# DogBLDC.net
KiCad netlist of a schematic drawn in Altium Designer
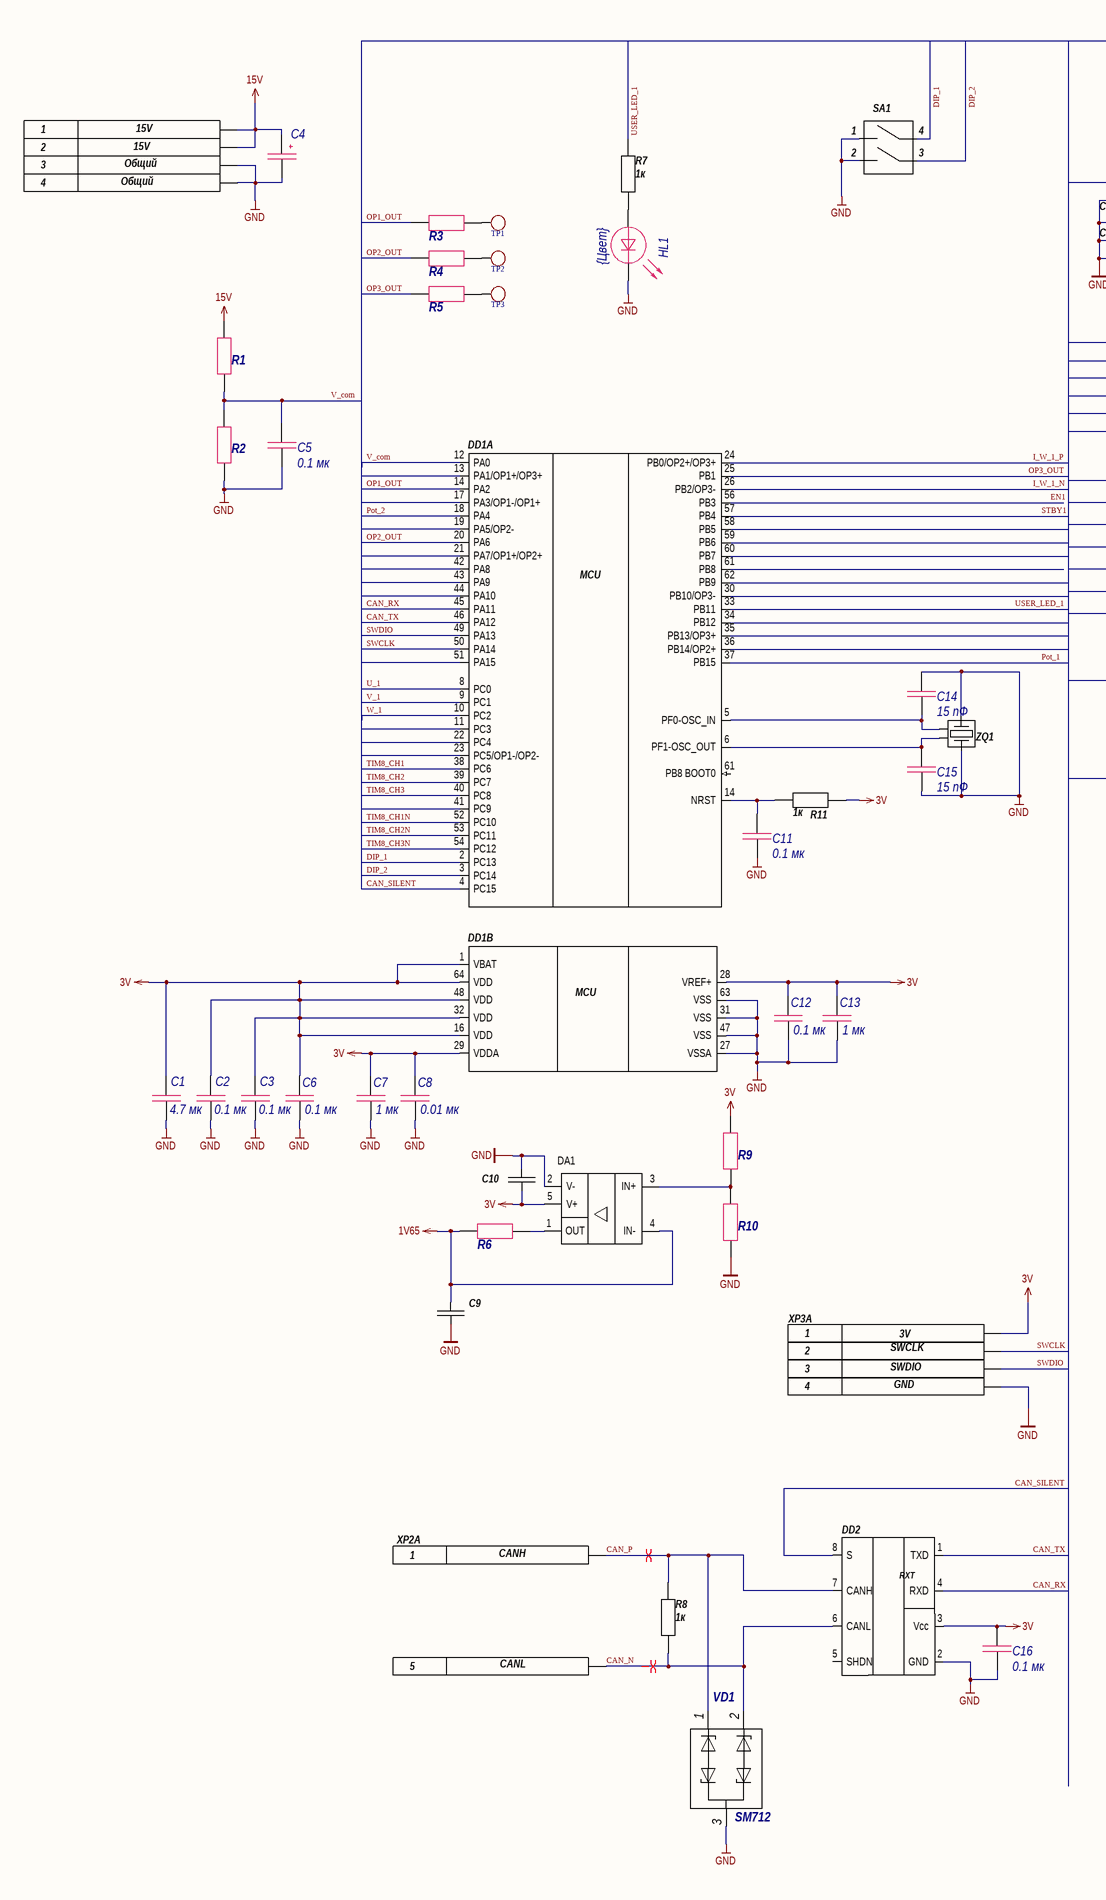
[diagram p0: DogBLDC.SchDoc, left]
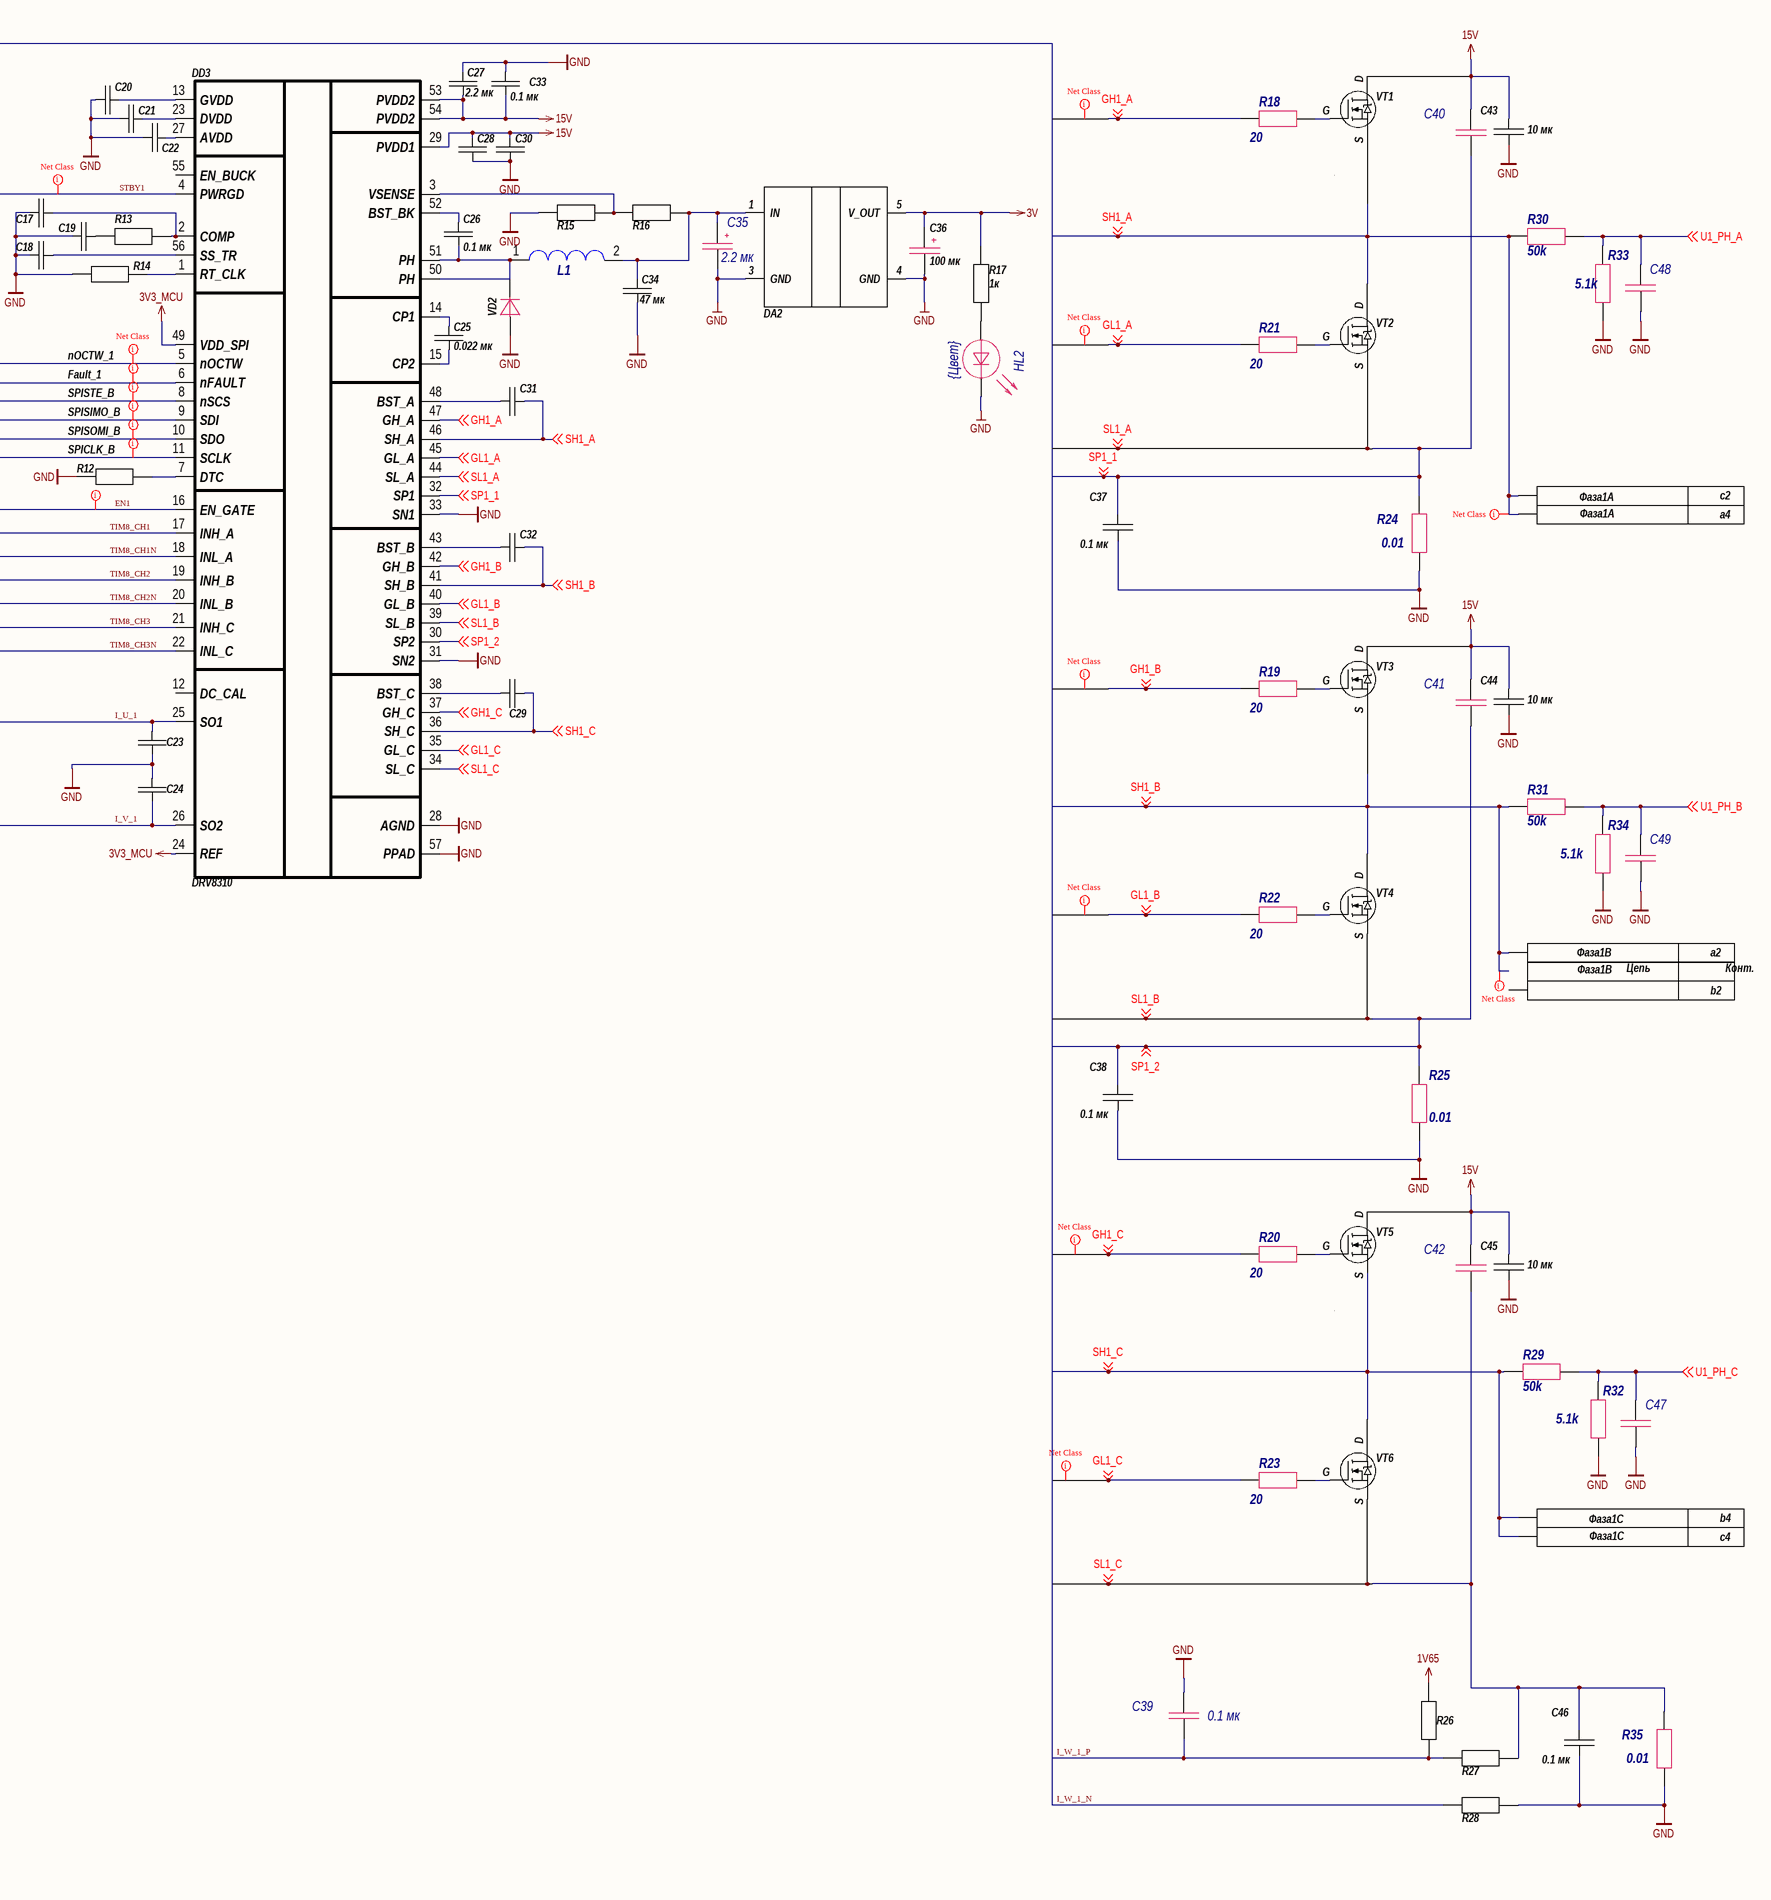
[diagram p1: DogBLDC.SchDoc, right]

(export (version "E")
  (design (tool "Eeschema 10.0.6"))
  (components
    (comp (ref "C1")
      (value "4.7 мк")
      (footprint "0603cap")
      (description "Capacitor")
      (libsource (lib "DogBLDC") (part "Capacitor"))
    )
    (comp (ref "C2")
      (value "0.1 мк")
      (footprint "0603cap")
      (description "Capacitor")
      (libsource (lib "DogBLDC") (part "Capacitor"))
    )
    (comp (ref "C3")
      (value "0.1 мк")
      (footprint "0603cap")
      (description "Capacitor")
      (libsource (lib "DogBLDC") (part "Capacitor"))
    )
    (comp (ref "C4")
      (value "1uF")
      (footprint "TC_B (3528)")
      (libsource (lib "DogBLDC") (part "Capacitor_pol"))
    )
    (comp (ref "C5")
      (value "0.1 мк")
      (footprint "0603c")
      (description "Capacitor")
      (libsource (lib "DogBLDC") (part "Capacitor"))
    )
    (comp (ref "C6")
      (value "0.1 мк")
      (footprint "0603cap")
      (description "Capacitor")
      (libsource (lib "DogBLDC") (part "Capacitor"))
    )
    (comp (ref "C7")
      (value "1 мк")
      (footprint "0603cap")
      (description "Capacitor")
      (libsource (lib "DogBLDC") (part "Capacitor"))
    )
    (comp (ref "C8")
      (value "0.01 мк")
      (footprint "0603cap")
      (description "Capacitor")
      (libsource (lib "DogBLDC") (part "Capacitor"))
    )
    (comp (ref "C9")
      (value "C_1")
      (footprint "RES 0402")
      (fields (field (name "TOLERANCE") "10 %"))
      (libsource (lib "DogBLDC") (part "C_1"))
    )
    (comp (ref "C10")
      (value "C_1")
      (footprint "RES 0402")
      (fields (field (name "TOLERANCE") "10 %"))
      (libsource (lib "DogBLDC") (part "C_1"))
    )
    (comp (ref "C11")
      (value "0.1 мк")
      (footprint "0603cap")
      (description "Capacitor")
      (libsource (lib "DogBLDC") (part "Capacitor"))
    )
    (comp (ref "C12")
      (value "0.1 мк")
      (footprint "0603cap")
      (description "Capacitor")
      (libsource (lib "DogBLDC") (part "Capacitor"))
    )
    (comp (ref "C13")
      (value "1 мк")
      (footprint "0603cap")
      (description "Capacitor")
      (libsource (lib "DogBLDC") (part "Capacitor"))
    )
    (comp (ref "C14")
      (value "15 пФ")
      (footprint "0603cap")
      (description "Capacitor")
      (libsource (lib "DogBLDC") (part "Capacitor"))
    )
    (comp (ref "C15")
      (value "15 пФ")
      (footprint "0603cap")
      (description "Capacitor")
      (libsource (lib "DogBLDC") (part "Capacitor"))
    )
    (comp (ref "C16")
      (value "0.1 мк")
      (footprint "0603cap")
      (description "Capacitor")
      (libsource (lib "DogBLDC") (part "Capacitor"))
    )
    (comp (ref "C17")
      (value "C_1")
      (footprint "RES 0402")
      (fields (field (name "TOLERANCE") "5 %"))
      (libsource (lib "DogBLDC") (part "C_1"))
    )
    (comp (ref "C18")
      (value "C_1")
      (footprint "RES 0402")
      (fields (field (name "TOLERANCE") "5 %"))
      (libsource (lib "DogBLDC") (part "C_1"))
    )
    (comp (ref "C19")
      (value "C_1")
      (footprint "RES 0402")
      (fields (field (name "TOLERANCE") "10 %"))
      (libsource (lib "DogBLDC") (part "C_1"))
    )
    (comp (ref "C20")
      (value "C_1")
      (footprint "0603c")
      (fields (field (name "TOLERANCE") "10 %"))
      (libsource (lib "DogBLDC") (part "C_1"))
    )
    (comp (ref "C21")
      (value "C_1")
      (footprint "0603c")
      (fields (field (name "TOLERANCE") "10 %"))
      (libsource (lib "DogBLDC") (part "C_1"))
    )
    (comp (ref "C22")
      (value "C_1")
      (footprint "0603c")
      (fields (field (name "TOLERANCE") "10 %"))
      (libsource (lib "DogBLDC") (part "C_1"))
    )
    (comp (ref "C23")
      (value "C_1")
      (footprint "RES 0402")
      (fields (field (name "TOLERANCE") "10 %"))
      (libsource (lib "DogBLDC") (part "C_1"))
    )
    (comp (ref "C24")
      (value "C_1")
      (footprint "RES 0402")
      (fields (field (name "TOLERANCE") "10 %"))
      (libsource (lib "DogBLDC") (part "C_1"))
    )
    (comp (ref "C25")
      (value "0.022 мк")
      (footprint "0805")
      (fields (field (name "TOLERANCE") "10 %") (field (name "Comment") "C_1"))
      (libsource (lib "DogBLDC") (part "C_1"))
    )
    (comp (ref "C26")
      (value "0.1 мк")
      (footprint "0603cap")
      (fields (field (name "TOLERANCE") "10 %") (field (name "Comment") "C_1"))
      (libsource (lib "DogBLDC") (part "C_1"))
    )
    (comp (ref "C27")
      (value "2.2 мк")
      (footprint "1206 - duplicate")
      (fields (field (name "TOLERANCE") "10 %") (field (name "Comment") "C_1"))
      (libsource (lib "DogBLDC") (part "C_1"))
    )
    (comp (ref "C28")
      (value "C_1")
      (footprint "0603cap")
      (fields (field (name "TOLERANCE") "10 %"))
      (libsource (lib "DogBLDC") (part "C_1"))
    )
    (comp (ref "C29")
      (value "C_1")
      (footprint "0603cap")
      (fields (field (name "TOLERANCE") "10 %"))
      (libsource (lib "DogBLDC") (part "C_1"))
    )
    (comp (ref "C30")
      (value "C_1")
      (footprint "0603cap")
      (fields (field (name "TOLERANCE") "10 %"))
      (libsource (lib "DogBLDC") (part "C_1"))
    )
    (comp (ref "C31")
      (value "C_1")
      (footprint "0603cap")
      (fields (field (name "TOLERANCE") "10 %"))
      (libsource (lib "DogBLDC") (part "C_1"))
    )
    (comp (ref "C32")
      (value "C_1")
      (footprint "0603cap")
      (fields (field (name "TOLERANCE") "10 %"))
      (libsource (lib "DogBLDC") (part "C_1"))
    )
    (comp (ref "C33")
      (value "0.1 мк")
      (footprint "0603cap")
      (fields (field (name "TOLERANCE") "10 %") (field (name "Comment") "C_1"))
      (libsource (lib "DogBLDC") (part "C_1"))
    )
    (comp (ref "C34")
      (value "47 мк")
      (footprint "1206 - duplicate")
      (fields (field (name "TOLERANCE") "10 %") (field (name "Comment") "C_1"))
      (libsource (lib "DogBLDC") (part "C_1"))
    )
    (comp (ref "C35")
      (value "2.2 мк")
      (footprint "TC_A (3216)")
      (fields (field (name "Comment") "1uF"))
      (libsource (lib "DogBLDC") (part "Capacitor_pol"))
    )
    (comp (ref "C36")
      (value "100 мк")
      (footprint "TC_D (7343)")
      (fields (field (name "TOLERANCE") "10 %") (field (name "Comment") "1uF"))
      (libsource (lib "DogBLDC") (part "Capacitor_pol"))
    )
    (comp (ref "C37")
      (value "0.1 мк")
      (footprint "0603C")
      (fields (field (name "TOLERANCE") "10 %"))
      (libsource (lib "DogBLDC") (part "C"))
    )
    (comp (ref "C38")
      (value "0.1 мк")
      (footprint "0603C")
      (fields (field (name "TOLERANCE") "10 %"))
      (libsource (lib "DogBLDC") (part "C"))
    )
    (comp (ref "C39")
      (value "0.1 мк")
      (footprint "0603C")
      (description "Capacitor")
      (fields (field (name "TOLERANCE") "10 %"))
      (libsource (lib "DogBLDC") (part "Capacitor"))
    )
    (comp (ref "C40")
      (value "Capacitor")
      (footprint "CAP_2220")
      (libsource (lib "DogBLDC") (part "Capacitor"))
    )
    (comp (ref "C41")
      (value "Capacitor")
      (footprint "CAP_2220")
      (libsource (lib "DogBLDC") (part "Capacitor"))
    )
    (comp (ref "C42")
      (value "Capacitor")
      (footprint "CAP_2220")
      (libsource (lib "DogBLDC") (part "Capacitor"))
    )
    (comp (ref "C43")
      (value "10 мк")
      (footprint "1812С")
      (fields (field (name "TOLERANCE") "10 %"))
      (libsource (lib "DogBLDC") (part "C"))
    )
    (comp (ref "C44")
      (value "10 мк")
      (footprint "1812С")
      (fields (field (name "TOLERANCE") "10 %"))
      (libsource (lib "DogBLDC") (part "C"))
    )
    (comp (ref "C45")
      (value "10 мк")
      (footprint "1812С")
      (fields (field (name "TOLERANCE") "10 %"))
      (libsource (lib "DogBLDC") (part "C"))
    )
    (comp (ref "C46")
      (value "0.1 мк")
      (footprint "0603C")
      (fields (field (name "TOLERANCE") "10 %"))
      (libsource (lib "DogBLDC") (part "C"))
    )
    (comp (ref "C47")
      (value "Capacitor")
      (footprint "RES 0402")
      (fields (field (name "TOLERANCE") "10 %"))
      (libsource (lib "DogBLDC") (part "Capacitor"))
    )
    (comp (ref "C48")
      (value "Capacitor")
      (footprint "RES 0402")
      (fields (field (name "TOLERANCE") "10 %"))
      (libsource (lib "DogBLDC") (part "Capacitor"))
    )
    (comp (ref "C49")
      (value "Capacitor")
      (footprint "RES 0402")
      (fields (field (name "TOLERANCE") "10 %"))
      (libsource (lib "DogBLDC") (part "Capacitor"))
    )
    (comp (ref "DA1") (value "TLV2781") (footprint "SOT23-5") (libsource (lib "DogBLDC") (part "TLV2781")))
    (comp (ref "DA2")
      (value "TPS7B9xx")
      (footprint "SOT23_6_Pin")
      (libsource (lib "DogBLDC") (part "TPS7B9xx"))
    )
    (comp (ref "DD1")
      (value "STM32G431x6")
      (footprint "STM-LQFP64_L")
      (fields (field (name "MANUFACTURER") "STMicroelectronics") (field (name "PARTNUMBER") "STM32F407VET6"))
      (libsource (lib "DogBLDC") (part "STM32G431x6"))
    )
    (comp (ref "DD2")
      (value "TCAN337DCN")
      (footprint "SOT23-8")
      (libsource (lib "DogBLDC") (part "TCAN337DCN"))
    )
    (comp (ref "DD3")
      (value "DRV8310")
      (footprint "TSSOP50P810X120_HS-57N")
      (libsource (lib "DogBLDC") (part "DRV8301"))
    )
    (comp (ref "HL1")
      (value "~")
      (footprint "0603D")
      (fields (field (name "COLOR") "{Цвет}"))
      (libsource (lib "DogBLDC") (part "LED"))
    )
    (comp (ref "HL2")
      (value "~")
      (footprint "0603D")
      (fields (field (name "COLOR") "{Цвет}"))
      (libsource (lib "DogBLDC") (part "LED"))
    )
    (comp (ref "L1")
      (value "DR74-330-R")
      (footprint "Inductor 6.3x6.3")
      (libsource (lib "DogBLDC") (part "Inductance"))
    )
    (comp (ref "R1")
      (value "Resistor")
      (footprint "RES 0402")
      (fields (field (name "TOLERANCE") "5 %"))
      (libsource (lib "") (part "Resistor_3"))
    )
    (comp (ref "R2")
      (value "Resistor")
      (footprint "RES 0402")
      (fields (field (name "TOLERANCE") "5 %"))
      (libsource (lib "") (part "Resistor_3"))
    )
    (comp (ref "R3")
      (value "Resistor")
      (footprint "RES 0402")
      (fields (field (name "TOLERANCE") "5 %"))
      (libsource (lib "") (part "Resistor_1"))
    )
    (comp (ref "R4")
      (value "Resistor")
      (footprint "RES 0402")
      (fields (field (name "TOLERANCE") "5 %"))
      (libsource (lib "") (part "Resistor_1"))
    )
    (comp (ref "R5")
      (value "Resistor")
      (footprint "RES 0402")
      (fields (field (name "TOLERANCE") "5 %"))
      (libsource (lib "") (part "Resistor_1"))
    )
    (comp (ref "R6")
      (value "Resistor")
      (footprint "RES 0402")
      (fields (field (name "TOLERANCE") "5 %"))
      (libsource (lib "") (part "Resistor_1"))
    )
    (comp (ref "R7")
      (value "1к")
      (footprint "0603res")
      (description "Resistor")
      (libsource (lib "") (part "Resistor_2"))
    )
    (comp (ref "R8")
      (value "1к")
      (footprint "0603res")
      (description "Resistor")
      (libsource (lib "") (part "Resistor_2"))
    )
    (comp (ref "R9")
      (value "Resistor")
      (footprint "RES 0402")
      (fields (field (name "TOLERANCE") "0.1%"))
      (libsource (lib "") (part "Resistor_2"))
    )
    (comp (ref "R10")
      (value "Resistor")
      (footprint "RES 0402")
      (fields (field (name "TOLERANCE") "0.1%"))
      (libsource (lib "") (part "Resistor_2"))
    )
    (comp (ref "R11")
      (value "1к")
      (footprint "0603res")
      (description "Resistor")
      (libsource (lib "") (part "Resistor_1"))
    )
    (comp (ref "R12")
      (value "Resistor")
      (footprint "RES 0402")
      (fields (field (name "TOLERANCE") "10 %"))
      (libsource (lib "DogBLDC") (part "Resistor"))
    )
    (comp (ref "R13")
      (value "Resistor")
      (footprint "RES 0402")
      (fields (field (name "TOLERANCE") "0.1 %"))
      (libsource (lib "DogBLDC") (part "Resistor"))
    )
    (comp (ref "R14")
      (value "Resistor")
      (footprint "RES 0402")
      (fields (field (name "TOLERANCE") "0.1 %"))
      (libsource (lib "DogBLDC") (part "Resistor"))
    )
    (comp (ref "R15")
      (value "Resistor")
      (footprint "0603RES")
      (fields (field (name "TOLERANCE") "1 %"))
      (libsource (lib "") (part "Resistor_1"))
    )
    (comp (ref "R16")
      (value "Resistor")
      (footprint "0603RES")
      (fields (field (name "TOLERANCE") "1 %"))
      (libsource (lib "") (part "Resistor_1"))
    )
    (comp (ref "R17")
      (value "1к")
      (footprint "0603res")
      (description "Resistor")
      (libsource (lib "") (part "Resistor_2"))
    )
    (comp (ref "R18")
      (value "20")
      (footprint "1206R")
      (fields (field (name "TOLERANCE") "10 %") (field (name "Comment") "Resistor"))
      (libsource (lib "DogBLDC") (part "Resistor"))
    )
    (comp (ref "R19")
      (value "20")
      (footprint "1206R")
      (fields (field (name "TOLERANCE") "10 %") (field (name "Comment") "Resistor"))
      (libsource (lib "DogBLDC") (part "Resistor"))
    )
    (comp (ref "R20")
      (value "20")
      (footprint "1206R")
      (fields (field (name "TOLERANCE") "10 %") (field (name "Comment") "Resistor"))
      (libsource (lib "DogBLDC") (part "Resistor"))
    )
    (comp (ref "R21")
      (value "20")
      (footprint "1206R")
      (fields (field (name "TOLERANCE") "10 %") (field (name "Comment") "Resistor"))
      (libsource (lib "DogBLDC") (part "Resistor"))
    )
    (comp (ref "R22")
      (value "20")
      (footprint "1206R")
      (fields (field (name "TOLERANCE") "10 %") (field (name "Comment") "Resistor"))
      (libsource (lib "DogBLDC") (part "Resistor"))
    )
    (comp (ref "R23")
      (value "20")
      (footprint "1206R")
      (fields (field (name "TOLERANCE") "10 %") (field (name "Comment") "Resistor"))
      (libsource (lib "DogBLDC") (part "Resistor"))
    )
    (comp (ref "R24")
      (value "0.01")
      (footprint "RES_LR2512")
      (fields (field (name "Comment") "Resistor"))
      (libsource (lib "") (part "Resistor_2"))
    )
    (comp (ref "R25")
      (value "0.01")
      (footprint "RES_LR2512")
      (fields (field (name "Comment") "Resistor"))
      (libsource (lib "") (part "Resistor_2"))
    )
    (comp (ref "R26")
      (value "Resistor")
      (footprint "RES 0402")
      (fields (field (name "TOLERANCE") "0.1%"))
      (libsource (lib "") (part "Resistor_2"))
    )
    (comp (ref "R27")
      (value "Resistor")
      (footprint "RES 0402")
      (fields (field (name "TOLERANCE") "0.1%"))
      (libsource (lib "DogBLDC") (part "Resistor"))
    )
    (comp (ref "R28")
      (value "Resistor")
      (footprint "RES 0402")
      (fields (field (name "TOLERANCE") "0.1%"))
      (libsource (lib "DogBLDC") (part "Resistor"))
    )
    (comp (ref "R29")
      (value "50k")
      (footprint "0603R")
      (fields (field (name "TOLERANCE") "1 %") (field (name "Comment") "Resistor"))
      (libsource (lib "DogBLDC") (part "Resistor"))
    )
    (comp (ref "R30")
      (value "50k")
      (footprint "0603R")
      (fields (field (name "TOLERANCE") "1 %") (field (name "Comment") "Resistor"))
      (libsource (lib "DogBLDC") (part "Resistor"))
    )
    (comp (ref "R31")
      (value "50k")
      (footprint "0603R")
      (fields (field (name "TOLERANCE") "1 %") (field (name "Comment") "Resistor"))
      (libsource (lib "DogBLDC") (part "Resistor"))
    )
    (comp (ref "R32")
      (value "5.1k")
      (footprint "0603R")
      (fields (field (name "TOLERANCE") "1 %") (field (name "Comment") "Resistor"))
      (libsource (lib "") (part "Resistor_3"))
    )
    (comp (ref "R33")
      (value "5.1k")
      (footprint "0603R")
      (fields (field (name "TOLERANCE") "1 %") (field (name "Comment") "Resistor"))
      (libsource (lib "") (part "Resistor_3"))
    )
    (comp (ref "R34")
      (value "5.1k")
      (footprint "0603R")
      (fields (field (name "TOLERANCE") "1 %") (field (name "Comment") "Resistor"))
      (libsource (lib "") (part "Resistor_3"))
    )
    (comp (ref "R35")
      (value "0.01")
      (footprint "RES_LR2512")
      (fields (field (name "Comment") "Resistor"))
      (libsource (lib "") (part "Resistor_2"))
    )
    (comp (ref "SA1")
      (value "DIP переключатель 2")
      (footprint "SW-2")
      (libsource (lib "DogBLDC") (part "DIP переключатель 2"))
    )
    (comp (ref "TP1")
      (value "TestPoint_1")
      (footprint "LensBox.SchDoc:TP1")
      (libsource (lib "DogBLDC") (part "TestPoint_1"))
    )
    (comp (ref "TP2")
      (value "TestPoint_1")
      (footprint "LensBox.SchDoc:TP1")
      (libsource (lib "DogBLDC") (part "TestPoint_1"))
    )
    (comp (ref "TP3")
      (value "TestPoint_1")
      (footprint "LensBox.SchDoc:TP1")
      (libsource (lib "DogBLDC") (part "TestPoint_1"))
    )
    (comp (ref "VD1") (value "SM712") (footprint "SOT23_true") (libsource (lib "DogBLDC") (part "SM712")))
    (comp (ref "VD2") (value "Diod") (footprint "SMB") (libsource (lib "DogBLDC") (part "Diod")))
    (comp (ref "VT1")
      (value "MOSFET GOST_PQFN5X6")
      (footprint "Power 5x6-8")
      (libsource (lib "DogBLDC") (part "MOSFET GOST_PQFN5X6"))
    )
    (comp (ref "VT2")
      (value "MOSFET GOST_PQFN5X6")
      (footprint "Power 5x6-8")
      (libsource (lib "DogBLDC") (part "MOSFET GOST_PQFN5X6"))
    )
    (comp (ref "VT3")
      (value "MOSFET GOST_PQFN5X6")
      (footprint "Power 5x6-8")
      (libsource (lib "DogBLDC") (part "MOSFET GOST_PQFN5X6"))
    )
    (comp (ref "VT4")
      (value "MOSFET GOST_PQFN5X6")
      (footprint "Power 5x6-8")
      (libsource (lib "DogBLDC") (part "MOSFET GOST_PQFN5X6"))
    )
    (comp (ref "VT5")
      (value "MOSFET GOST_PQFN5X6")
      (footprint "Power 5x6-8")
      (libsource (lib "DogBLDC") (part "MOSFET GOST_PQFN5X6"))
    )
    (comp (ref "VT6")
      (value "MOSFET GOST_PQFN5X6")
      (footprint "Power 5x6-8")
      (libsource (lib "DogBLDC") (part "MOSFET GOST_PQFN5X6"))
    )
    (comp (ref "XP1")
      (value "Конт.6_Вилка_ отд.контакты")
      (footprint "G125-MS10605L3P")
      (fields (field (name "VALUE7") "15V") (field (name "VALUE5") "Общий") (field (name "VALUE9") "CANL"))
      (libsource (lib "DogBLDC") (part "Конт.6_Вилка_ отд.контакты"))
    )
    (comp (ref "XP2")
      (value "Конт.6_Вилка_ отд.контакты")
      (footprint "G125-MS10605L3P")
      (fields (field (name "VALUE1") "CANH"))
      (libsource (lib "DogBLDC") (part "Конт.6_Вилка_ отд.контакты"))
    )
    (comp (ref "XP3")
      (value "Конт.4_Single")
      (footprint "PLL4")
      (fields
        (field (name "VALUE1") "3V")
        (field (name "VALUE2") "SWCLK")
        (field (name "VALUE3") "SWDIO")
        (field (name "VALUE4") "GND")
      )
      (libsource (lib "DogBLDC") (part "Конт.4_Single_1"))
    )
    (comp (ref "XP4")
      (value "Конт.48_Вилка_ отд.контакты")
      (footprint "DIN-Power E048MR-3,0C1-2-right_numbers")
      (libsource (lib "DogBLDC") (part "Конт.48_Вилка_ отд.контакты"))
    )
    (comp (ref "ZQ1") (value "KX-7") (footprint "kx-7") (libsource (lib "DogBLDC") (part "XTAL_4(KX-7)")))
  )
  (nets
    (net (code "1") (name "/CAN_N") (class "Default")
      (node (ref "DD2") (pin "6") (pinfunction "CANL_6") (pintype "passive"))
      (node (ref "R8") (pin "1") (pinfunction "1_1") (pintype "passive"))
      (node (ref "VD1") (pin "2") (pinfunction "IN2_2") (pintype "passive"))
      (node (ref "XP1") (pin "5") (pinfunction "5_5") (pintype "passive"))
    )
    (net (code "2") (name "/CAN_P") (class "Default")
      (node (ref "DD2") (pin "7") (pinfunction "CANH_7") (pintype "passive"))
      (node (ref "R8") (pin "2") (pinfunction "2_2") (pintype "passive"))
      (node (ref "VD1") (pin "1") (pinfunction "IN1_1") (pintype "passive"))
      (node (ref "XP2") (pin "1") (pinfunction "1_1") (pintype "passive"))
    )
    (net (code "3") (name "/CAN_RX") (class "Default")
      (node (ref "DD1") (pin "45") (pinfunction "PA11_45") (pintype "bidirectional"))
      (node (ref "DD2") (pin "4") (pinfunction "RXD_4") (pintype "passive"))
    )
    (net (code "4") (name "/CAN_SILENT") (class "Default")
      (node (ref "DD1") (pin "4") (pinfunction "PC15_4") (pintype "bidirectional"))
      (node (ref "DD2") (pin "8") (pinfunction "S_8") (pintype "passive"))
    )
    (net (code "5") (name "/CAN_TX") (class "Default")
      (node (ref "DD1") (pin "46") (pinfunction "PA12_46") (pintype "bidirectional"))
      (node (ref "DD2") (pin "1") (pinfunction "TXD_1") (pintype "passive"))
    )
    (net (code "6") (name "/DIP_1") (class "Default")
      (node (ref "DD1") (pin "2") (pinfunction "PC13_2") (pintype "bidirectional"))
      (node (ref "SA1") (pin "4") (pinfunction "4_4") (pintype "passive"))
    )
    (net (code "7") (name "/DIP_2") (class "Default")
      (node (ref "DD1") (pin "3") (pinfunction "PC14_3") (pintype "bidirectional"))
      (node (ref "SA1") (pin "3") (pinfunction "3_3") (pintype "passive"))
    )
    (net (code "8") (name "/EN1") (class "Default")
      (node (ref "DD1") (pin "56") (pinfunction "PB3_56") (pintype "bidirectional"))
      (node (ref "DD3") (pin "16") (pinfunction "EN_GATE_16") (pintype "passive"))
    )
    (net (code "9") (name "/Fault_1") (class "Default")
      (node (ref "DD3") (pin "6") (pinfunction "nFAULT_6") (pintype "passive"))
    )
    (net (code "10") (name "/I_U_1") (class "Default")
      (node (ref "C23") (pin "1") (pinfunction "1_1") (pintype "passive"))
      (node (ref "DD3") (pin "25") (pinfunction "SO1_25") (pintype "passive"))
    )
    (net (code "11") (name "/I_V_1") (class "Default")
      (node (ref "C24") (pin "2") (pinfunction "2_2") (pintype "passive"))
      (node (ref "DD3") (pin "26") (pinfunction "SO2_26") (pintype "passive"))
    )
    (net (code "12") (name "/I_W_1_N") (class "Default")
      (node (ref "DD1") (pin "26") (pinfunction "PB2/OP3-_26") (pintype "bidirectional"))
      (node (ref "R28") (pin "1") (pinfunction "1_1") (pintype "passive"))
    )
    (net (code "13") (name "/I_W_1_P") (class "Default")
      (node (ref "C39") (pin "2") (pinfunction "2_2") (pintype "passive"))
      (node (ref "DD1") (pin "24") (pinfunction "PB0/OP2+/OP3+_24") (pintype "bidirectional"))
      (node (ref "R26") (pin "1") (pinfunction "1_1") (pintype "passive"))
      (node (ref "R27") (pin "1") (pinfunction "1_1") (pintype "passive"))
    )
    (net (code "14") (name "/OP1_OUT") (class "Default")
      (node (ref "DD1") (pin "14") (pinfunction "PA2_14") (pintype "bidirectional"))
      (node (ref "R3") (pin "2") (pinfunction "2_2") (pintype "passive"))
    )
    (net (code "15") (name "/OP2_OUT") (class "Default")
      (node (ref "DD1") (pin "20") (pinfunction "PA6_20") (pintype "bidirectional"))
      (node (ref "R4") (pin "2") (pinfunction "2_2") (pintype "passive"))
    )
    (net (code "16") (name "/OP3_OUT") (class "Default")
      (node (ref "DD1") (pin "25") (pinfunction "PB1_25") (pintype "bidirectional"))
      (node (ref "R5") (pin "2") (pinfunction "2_2") (pintype "passive"))
    )
    (net (code "17") (name "/Pot_1") (class "Default")
      (node (ref "DD1") (pin "37") (pinfunction "PB15_37") (pintype "bidirectional"))
    )
    (net (code "18") (name "/Pot_2") (class "Default")
      (node (ref "DD1") (pin "18") (pinfunction "PA4_18") (pintype "bidirectional"))
    )
    (net (code "19") (name "/SPICLK_B") (class "Default")
      (node (ref "DD3") (pin "11") (pinfunction "SCLK_11") (pintype "passive"))
    )
    (net (code "20") (name "/SPISIMO_B") (class "Default")
      (node (ref "DD3") (pin "9") (pinfunction "SDI_9") (pintype "passive"))
    )
    (net (code "21") (name "/SPISOMI_B") (class "Default")
      (node (ref "DD3") (pin "10") (pinfunction "SDO_10") (pintype "passive"))
    )
    (net (code "22") (name "/SPISTE_B") (class "Default")
      (node (ref "DD3") (pin "8") (pinfunction "nSCS_8") (pintype "passive"))
    )
    (net (code "23") (name "/STBY1") (class "Default")
      (node (ref "DD1") (pin "57") (pinfunction "PB4_57") (pintype "bidirectional"))
      (node (ref "DD3") (pin "4") (pinfunction "PWRGD_4") (pintype "passive"))
    )
    (net (code "24") (name "/SWCLK") (class "Default")
      (node (ref "DD1") (pin "50") (pinfunction "PA14_50") (pintype "bidirectional"))
      (node (ref "XP3") (pin "2") (pinfunction "2_2") (pintype "passive"))
    )
    (net (code "25") (name "/SWDIO") (class "Default")
      (node (ref "DD1") (pin "49") (pinfunction "PA13_49") (pintype "bidirectional"))
      (node (ref "XP3") (pin "3") (pinfunction "3_3") (pintype "passive"))
    )
    (net (code "26") (name "/TIM8_CH1") (class "Default")
      (node (ref "DD1") (pin "38") (pinfunction "PC6_38") (pintype "bidirectional"))
      (node (ref "DD3") (pin "17") (pinfunction "INH_A_17") (pintype "passive"))
    )
    (net (code "27") (name "/TIM8_CH1N") (class "Default")
      (node (ref "DD1") (pin "52") (pinfunction "PC10_52") (pintype "bidirectional"))
      (node (ref "DD3") (pin "18") (pinfunction "INL_A_18") (pintype "passive"))
    )
    (net (code "28") (name "/TIM8_CH2") (class "Default")
      (node (ref "DD1") (pin "39") (pinfunction "PC7_39") (pintype "bidirectional"))
      (node (ref "DD3") (pin "19") (pinfunction "INH_B_19") (pintype "passive"))
    )
    (net (code "29") (name "/TIM8_CH2N") (class "Default")
      (node (ref "DD1") (pin "53") (pinfunction "PC11_53") (pintype "bidirectional"))
      (node (ref "DD3") (pin "20") (pinfunction "INL_B_20") (pintype "passive"))
    )
    (net (code "30") (name "/TIM8_CH3") (class "Default")
      (node (ref "DD1") (pin "40") (pinfunction "PC8_40") (pintype "bidirectional"))
      (node (ref "DD3") (pin "21") (pinfunction "INH_C_21") (pintype "passive"))
    )
    (net (code "31") (name "/TIM8_CH3N") (class "Default")
      (node (ref "DD1") (pin "54") (pinfunction "PC12_54") (pintype "bidirectional"))
      (node (ref "DD3") (pin "22") (pinfunction "INL_C_22") (pintype "passive"))
    )
    (net (code "32") (name "/USER_LED_1") (class "Default")
      (node (ref "DD1") (pin "33") (pinfunction "PB11_33") (pintype "bidirectional"))
      (node (ref "R7") (pin "2") (pinfunction "2_2") (pintype "passive"))
    )
    (net (code "33") (name "/U_1") (class "Default")
      (node (ref "DD1") (pin "8") (pinfunction "PC0_8") (pintype "bidirectional"))
    )
    (net (code "34") (name "/V_1") (class "Default")
      (node (ref "DD1") (pin "9") (pinfunction "PC1_9") (pintype "bidirectional"))
    )
    (net (code "35") (name "/V_com") (class "Default")
      (node (ref "C5") (pin "2") (pinfunction "2_2") (pintype "passive"))
      (node (ref "DD1") (pin "12") (pinfunction "PA0_12") (pintype "bidirectional"))
      (node (ref "R1") (pin "2") (pinfunction "2_2") (pintype "passive"))
      (node (ref "R2") (pin "1") (pinfunction "1_1") (pintype "passive"))
    )
    (net (code "36") (name "/W_1") (class "Default")
      (node (ref "DD1") (pin "10") (pinfunction "PC2_10") (pintype "bidirectional"))
    )
    (net (code "37") (name "/nOCTW_1") (class "Default")
      (node (ref "DD3") (pin "5") (pinfunction "nOCTW_5") (pintype "passive"))
    )
    (net (code "44") (name "1V65") (class "Default")
      (node (ref "C9") (pin "1") (pinfunction "1_1") (pintype "passive"))
      (node (ref "DA1") (pin "4") (pinfunction "IN-_4") (pintype "passive"))
      (node (ref "R26") (pin "2") (pinfunction "2_2") (pintype "passive"))
      (node (ref "R6") (pin "2") (pinfunction "2_2") (pintype "passive"))
    )
    (net (code "45") (name "3V") (class "Default")
      (node (ref "C1") (pin "2") (pinfunction "2_2") (pintype "passive"))
      (node (ref "C10") (pin "2") (pinfunction "2_2") (pintype "passive"))
      (node (ref "C12") (pin "2") (pinfunction "2_2") (pintype "passive"))
      (node (ref "C13") (pin "2") (pinfunction "2_2") (pintype "passive"))
      (node (ref "C16") (pin "2") (pinfunction "2_2") (pintype "passive"))
      (node (ref "C2") (pin "2") (pinfunction "2_2") (pintype "passive"))
      (node (ref "C3") (pin "2") (pinfunction "2_2") (pintype "passive"))
      (node (ref "C36") (pin "1") (pinfunction "1_1") (pintype "passive"))
      (node (ref "C6") (pin "2") (pinfunction "2_2") (pintype "passive"))
      (node (ref "C7") (pin "2") (pinfunction "2_2") (pintype "passive"))
      (node (ref "C8") (pin "2") (pinfunction "2_2") (pintype "passive"))
      (node (ref "DA1") (pin "5") (pinfunction "V+_5") (pintype "power_in"))
      (node (ref "DA2") (pin "5") (pinfunction "V_OUT_5") (pintype "passive"))
      (node (ref "DD1") (pin "1") (pinfunction "VBAT_1") (pintype "power_in"))
      (node (ref "DD1") (pin "16") (pinfunction "VDD_16") (pintype "power_in"))
      (node (ref "DD1") (pin "28") (pinfunction "VREF+_28") (pintype "power_in"))
      (node (ref "DD1") (pin "29") (pinfunction "VDDA_29") (pintype "power_in"))
      (node (ref "DD1") (pin "32") (pinfunction "VDD_32") (pintype "power_in"))
      (node (ref "DD1") (pin "48") (pinfunction "VDD_48") (pintype "power_in"))
      (node (ref "DD1") (pin "64") (pinfunction "VDD_64") (pintype "power_in"))
      (node (ref "DD2") (pin "3") (pinfunction "Vcc_3") (pintype "passive"))
      (node (ref "R11") (pin "1") (pinfunction "1_1") (pintype "passive"))
      (node (ref "R17") (pin "2") (pinfunction "2_2") (pintype "passive"))
      (node (ref "R9") (pin "2") (pinfunction "2_2") (pintype "passive"))
      (node (ref "XP3") (pin "1") (pinfunction "1_1") (pintype "passive"))
    )
    (net (code "46") (name "3V3_MCU") (class "Default")
      (node (ref "DD3") (pin "24") (pinfunction "REF_24") (pintype "passive"))
      (node (ref "DD3") (pin "49") (pinfunction "VDD_SPI_49") (pintype "passive"))
    )
    (net (code "47") (name "15V") (class "Default")
      (node (ref "C27") (pin "1") (pinfunction "1_1") (pintype "passive"))
      (node (ref "C28") (pin "2") (pinfunction "2_2") (pintype "passive"))
      (node (ref "C30") (pin "2") (pinfunction "2_2") (pintype "passive"))
      (node (ref "C33") (pin "1") (pinfunction "1_1") (pintype "passive"))
      (node (ref "C4") (pin "1") (pinfunction "1_1") (pintype "passive"))
      (node (ref "C40") (pin "1") (pinfunction "1_1") (pintype "passive"))
      (node (ref "C41") (pin "1") (pinfunction "1_1") (pintype "passive"))
      (node (ref "C42") (pin "1") (pinfunction "1_1") (pintype "passive"))
      (node (ref "C43") (pin "1") (pinfunction "1_1") (pintype "passive"))
      (node (ref "C44") (pin "1") (pinfunction "1_1") (pintype "passive"))
      (node (ref "C45") (pin "1") (pinfunction "1_1") (pintype "passive"))
      (node (ref "DD3") (pin "29") (pinfunction "PVDD1_29") (pintype "passive"))
      (node (ref "DD3") (pin "53") (pinfunction "PVDD2_53") (pintype "passive"))
      (node (ref "DD3") (pin "54") (pinfunction "PVDD2_54") (pintype "passive"))
      (node (ref "R1") (pin "1") (pinfunction "1_1") (pintype "passive"))
      (node (ref "VT1") (pin "D") (pinfunction "135_D") (pintype "passive"))
      (node (ref "VT3") (pin "D") (pinfunction "135_D") (pintype "passive"))
      (node (ref "VT5") (pin "D") (pinfunction "135_D") (pintype "passive"))
      (node (ref "XP1") (pin "1") (pinfunction "1_1") (pintype "passive"))
      (node (ref "XP1") (pin "2") (pinfunction "2_2") (pintype "passive"))
    )
    (net (code "48") (name "GH1_A") (class "Default")
      (node (ref "DD3") (pin "47") (pinfunction "GH_A_47") (pintype "passive"))
      (node (ref "R18") (pin "1") (pinfunction "1_1") (pintype "passive"))
    )
    (net (code "49") (name "GH1_B") (class "Default")
      (node (ref "DD3") (pin "42") (pinfunction "GH_B_42") (pintype "passive"))
      (node (ref "R19") (pin "1") (pinfunction "1_1") (pintype "passive"))
    )
    (net (code "50") (name "GH1_C") (class "Default")
      (node (ref "DD3") (pin "37") (pinfunction "GH_C_37") (pintype "passive"))
      (node (ref "R20") (pin "1") (pinfunction "1_1") (pintype "passive"))
    )
    (net (code "51") (name "GL1_A") (class "Default")
      (node (ref "DD3") (pin "45") (pinfunction "GL_A_45") (pintype "passive"))
      (node (ref "R21") (pin "1") (pinfunction "1_1") (pintype "passive"))
    )
    (net (code "52") (name "GL1_B") (class "Default")
      (node (ref "DD3") (pin "40") (pinfunction "GL_B_40") (pintype "passive"))
      (node (ref "R22") (pin "1") (pinfunction "1_1") (pintype "passive"))
    )
    (net (code "53") (name "GL1_C") (class "Default")
      (node (ref "DD3") (pin "35") (pinfunction "GL_C_35") (pintype "passive"))
      (node (ref "R23") (pin "1") (pinfunction "1_1") (pintype "passive"))
    )
    (net (code "54") (name "GND") (class "Default")
      (node (ref "C1") (pin "1") (pinfunction "1_1") (pintype "passive"))
      (node (ref "C10") (pin "1") (pinfunction "1_1") (pintype "passive"))
      (node (ref "C11") (pin "1") (pinfunction "1_1") (pintype "passive"))
      (node (ref "C12") (pin "1") (pinfunction "1_1") (pintype "passive"))
      (node (ref "C13") (pin "1") (pinfunction "1_1") (pintype "passive"))
      (node (ref "C14") (pin "2") (pinfunction "2_2") (pintype "passive"))
      (node (ref "C15") (pin "1") (pinfunction "1_1") (pintype "passive"))
      (node (ref "C16") (pin "1") (pinfunction "1_1") (pintype "passive"))
      (node (ref "C17") (pin "2") (pinfunction "2_2") (pintype "passive"))
      (node (ref "C18") (pin "2") (pinfunction "2_2") (pintype "passive"))
      (node (ref "C19") (pin "2") (pinfunction "2_2") (pintype "passive"))
      (node (ref "C2") (pin "1") (pinfunction "1_1") (pintype "passive"))
      (node (ref "C20") (pin "1") (pinfunction "1_1") (pintype "passive"))
      (node (ref "C21") (pin "1") (pinfunction "1_1") (pintype "passive"))
      (node (ref "C22") (pin "1") (pinfunction "1_1") (pintype "passive"))
      (node (ref "C23") (pin "2") (pinfunction "2_2") (pintype "passive"))
      (node (ref "C24") (pin "1") (pinfunction "1_1") (pintype "passive"))
      (node (ref "C27") (pin "2") (pinfunction "2_2") (pintype "passive"))
      (node (ref "C28") (pin "1") (pinfunction "1_1") (pintype "passive"))
      (node (ref "C3") (pin "1") (pinfunction "1_1") (pintype "passive"))
      (node (ref "C30") (pin "1") (pinfunction "1_1") (pintype "passive"))
      (node (ref "C33") (pin "2") (pinfunction "2_2") (pintype "passive"))
      (node (ref "C34") (pin "1") (pinfunction "1_1") (pintype "passive"))
      (node (ref "C35") (pin "2") (pinfunction "2_2") (pintype "passive"))
      (node (ref "C36") (pin "2") (pinfunction "2_2") (pintype "passive"))
      (node (ref "C37") (pin "2") (pinfunction "2_2") (pintype "passive"))
      (node (ref "C38") (pin "2") (pinfunction "2_2") (pintype "passive"))
      (node (ref "C39") (pin "1") (pinfunction "1_1") (pintype "passive"))
      (node (ref "C4") (pin "2") (pinfunction "2_2") (pintype "passive"))
      (node (ref "C43") (pin "2") (pinfunction "2_2") (pintype "passive"))
      (node (ref "C44") (pin "2") (pinfunction "2_2") (pintype "passive"))
      (node (ref "C45") (pin "2") (pinfunction "2_2") (pintype "passive"))
      (node (ref "C46") (pin "2") (pinfunction "2_2") (pintype "passive"))
      (node (ref "C47") (pin "2") (pinfunction "2_2") (pintype "passive"))
      (node (ref "C48") (pin "2") (pinfunction "2_2") (pintype "passive"))
      (node (ref "C49") (pin "2") (pinfunction "2_2") (pintype "passive"))
      (node (ref "C5") (pin "1") (pinfunction "1_1") (pintype "passive"))
      (node (ref "C6") (pin "1") (pinfunction "1_1") (pintype "passive"))
      (node (ref "C7") (pin "1") (pinfunction "1_1") (pintype "passive"))
      (node (ref "C8") (pin "1") (pinfunction "1_1") (pintype "passive"))
      (node (ref "C9") (pin "2") (pinfunction "2_2") (pintype "passive"))
      (node (ref "DA1") (pin "2") (pinfunction "V-_2") (pintype "power_in"))
      (node (ref "DA2") (pin "3") (pinfunction "GND_3") (pintype "passive"))
      (node (ref "DA2") (pin "4") (pinfunction "GND_4") (pintype "passive"))
      (node (ref "DD1") (pin "27") (pinfunction "VSSA_27") (pintype "power_in"))
      (node (ref "DD1") (pin "31") (pinfunction "VSS_31") (pintype "power_in"))
      (node (ref "DD1") (pin "47") (pinfunction "VSS_47") (pintype "power_in"))
      (node (ref "DD1") (pin "63") (pinfunction "VSS_63") (pintype "power_in"))
      (node (ref "DD2") (pin "2") (pinfunction "GND_2") (pintype "passive"))
      (node (ref "DD3") (pin "28") (pinfunction "AGND_28") (pintype "passive"))
      (node (ref "DD3") (pin "31") (pinfunction "SN2_31") (pintype "passive"))
      (node (ref "DD3") (pin "33") (pinfunction "SN1_33") (pintype "passive"))
      (node (ref "DD3") (pin "57") (pinfunction "PPAD_57") (pintype "passive"))
      (node (ref "HL1") (pin "2") (pinfunction "2_2") (pintype "passive"))
      (node (ref "HL2") (pin "2") (pinfunction "2_2") (pintype "passive"))
      (node (ref "R10") (pin "1") (pinfunction "1_1") (pintype "passive"))
      (node (ref "R12") (pin "1") (pinfunction "1_1") (pintype "passive"))
      (node (ref "R14") (pin "1") (pinfunction "1_1") (pintype "passive"))
      (node (ref "R15") (pin "2") (pinfunction "2_2") (pintype "passive"))
      (node (ref "R2") (pin "2") (pinfunction "2_2") (pintype "passive"))
      (node (ref "R24") (pin "1") (pinfunction "1_1") (pintype "passive"))
      (node (ref "R25") (pin "1") (pinfunction "1_1") (pintype "passive"))
      (node (ref "R28") (pin "2") (pinfunction "2_2") (pintype "passive"))
      (node (ref "R32") (pin "2") (pinfunction "2_2") (pintype "passive"))
      (node (ref "R33") (pin "2") (pinfunction "2_2") (pintype "passive"))
      (node (ref "R34") (pin "2") (pinfunction "2_2") (pintype "passive"))
      (node (ref "R35") (pin "1") (pinfunction "1_1") (pintype "passive"))
      (node (ref "SA1") (pin "1") (pinfunction "1_1") (pintype "passive"))
      (node (ref "SA1") (pin "2") (pinfunction "2_2") (pintype "passive"))
      (node (ref "VD1") (pin "3") (pinfunction "GND_3") (pintype "passive"))
      (node (ref "VD2") (pin "1") (pinfunction "1_1") (pintype "passive"))
      (node (ref "XP1") (pin "3") (pinfunction "3_3") (pintype "passive"))
      (node (ref "XP1") (pin "4") (pinfunction "4_4") (pintype "passive"))
      (node (ref "XP3") (pin "4") (pinfunction "4_4") (pintype "passive"))
      (node (ref "ZQ1") (pin "1") (pinfunction "XTAL1_1") (pintype "passive"))
      (node (ref "ZQ1") (pin "3") (pinfunction "XTAL2_3") (pintype "passive"))
    )
    (net (code "55") (name "Net-(C19-Pad1)") (class "Default")
      (node (ref "C19") (pin "1") (pinfunction "1_1") (pintype "passive"))
      (node (ref "R13") (pin "1") (pinfunction "1_1") (pintype "passive"))
    )
    (net (code "56") (name "Net-(C26-Pad1)") (class "Default")
      (node (ref "C26") (pin "1") (pinfunction "1_1") (pintype "passive"))
      (node (ref "DD3") (pin "50") (pinfunction "PH_50") (pintype "passive"))
      (node (ref "DD3") (pin "51") (pinfunction "PH_51") (pintype "passive"))
      (node (ref "L1") (pin "1") (pinfunction "1_1") (pintype "passive"))
      (node (ref "VD2") (pin "2") (pinfunction "2_2") (pintype "passive"))
    )
    (net (code "57") (name "Net-(DA1-IN+)") (class "Default")
      (node (ref "DA1") (pin "3") (pinfunction "IN+_3") (pintype "passive"))
      (node (ref "R10") (pin "2") (pinfunction "2_2") (pintype "passive"))
      (node (ref "R9") (pin "1") (pinfunction "1_1") (pintype "passive"))
    )
    (net (code "58") (name "Net-(DA1-OUT)") (class "Default")
      (node (ref "DA1") (pin "1") (pinfunction "OUT_1") (pintype "passive"))
      (node (ref "R6") (pin "1") (pinfunction "1_1") (pintype "passive"))
    )
    (net (code "59") (name "Net-(DA2-IN)") (class "Default")
      (node (ref "C34") (pin "2") (pinfunction "2_2") (pintype "passive"))
      (node (ref "C35") (pin "1") (pinfunction "1_1") (pintype "passive"))
      (node (ref "DA2") (pin "1") (pinfunction "IN_1") (pintype "passive"))
      (node (ref "L1") (pin "2") (pinfunction "2_2") (pintype "passive"))
      (node (ref "R16") (pin "1") (pinfunction "1_1") (pintype "passive"))
    )
    (net (code "60") (name "Net-(DD1A-NRST)") (class "Default")
      (node (ref "C11") (pin "2") (pinfunction "2_2") (pintype "passive"))
      (node (ref "DD1") (pin "14") (pinfunction "NRST_14") (pintype "bidirectional"))
      (node (ref "R11") (pin "2") (pinfunction "2_2") (pintype "passive"))
    )
    (net (code "61") (name "Net-(DD1A-PF0-OSC_IN)") (class "Default")
      (node (ref "C14") (pin "1") (pinfunction "1_1") (pintype "passive"))
      (node (ref "DD1") (pin "5") (pinfunction "PF0-OSC_IN_5") (pintype "bidirectional"))
      (node (ref "ZQ1") (pin "4") (pinfunction "XTAL2_4") (pintype "passive"))
    )
    (net (code "62") (name "Net-(DD1A-PF1-OSC_OUT)") (class "Default")
      (node (ref "C15") (pin "2") (pinfunction "2_2") (pintype "passive"))
      (node (ref "DD1") (pin "6") (pinfunction "PF1-OSC_OUT_6") (pintype "bidirectional"))
      (node (ref "ZQ1") (pin "2") (pinfunction "XTAL2_2") (pintype "passive"))
    )
    (net (code "63") (name "Net-(DD3-AVDD)") (class "Default")
      (node (ref "C22") (pin "2") (pinfunction "2_2") (pintype "passive"))
      (node (ref "DD3") (pin "27") (pinfunction "AVDD_27") (pintype "passive"))
    )
    (net (code "64") (name "Net-(DD3-BST_A)") (class "Default")
      (node (ref "C31") (pin "2") (pinfunction "2_2") (pintype "passive"))
      (node (ref "DD3") (pin "48") (pinfunction "BST_A_48") (pintype "passive"))
    )
    (net (code "65") (name "Net-(DD3-BST_B)") (class "Default")
      (node (ref "C32") (pin "2") (pinfunction "2_2") (pintype "passive"))
      (node (ref "DD3") (pin "43") (pinfunction "BST_B_43") (pintype "passive"))
    )
    (net (code "66") (name "Net-(DD3-BST_BK)") (class "Default")
      (node (ref "C26") (pin "2") (pinfunction "2_2") (pintype "passive"))
      (node (ref "DD3") (pin "52") (pinfunction "BST_BK_52") (pintype "passive"))
    )
    (net (code "67") (name "Net-(DD3-BST_C)") (class "Default")
      (node (ref "C29") (pin "2") (pinfunction "2_2") (pintype "passive"))
      (node (ref "DD3") (pin "38") (pinfunction "BST_C_38") (pintype "passive"))
    )
    (net (code "68") (name "Net-(DD3-COMP)") (class "Default")
      (node (ref "C17") (pin "1") (pinfunction "1_1") (pintype "passive"))
      (node (ref "DD3") (pin "2") (pinfunction "COMP_2") (pintype "passive"))
      (node (ref "R13") (pin "2") (pinfunction "2_2") (pintype "passive"))
    )
    (net (code "69") (name "Net-(DD3-CP1)") (class "Default")
      (node (ref "C25") (pin "2") (pinfunction "2_2") (pintype "passive"))
      (node (ref "DD3") (pin "14") (pinfunction "CP1_14") (pintype "passive"))
    )
    (net (code "70") (name "Net-(DD3-CP2)") (class "Default")
      (node (ref "C25") (pin "1") (pinfunction "1_1") (pintype "passive"))
      (node (ref "DD3") (pin "15") (pinfunction "CP2_15") (pintype "passive"))
    )
    (net (code "71") (name "Net-(DD3-DTC)") (class "Default")
      (node (ref "DD3") (pin "7") (pinfunction "DTC_7") (pintype "passive"))
      (node (ref "R12") (pin "2") (pinfunction "2_2") (pintype "passive"))
    )
    (net (code "72") (name "Net-(DD3-DVDD)") (class "Default")
      (node (ref "C21") (pin "2") (pinfunction "2_2") (pintype "passive"))
      (node (ref "DD3") (pin "23") (pinfunction "DVDD_23") (pintype "passive"))
    )
    (net (code "73") (name "Net-(DD3-GVDD)") (class "Default")
      (node (ref "C20") (pin "2") (pinfunction "2_2") (pintype "passive"))
      (node (ref "DD3") (pin "13") (pinfunction "GVDD_13") (pintype "passive"))
    )
    (net (code "74") (name "Net-(DD3-RT_CLK)") (class "Default")
      (node (ref "DD3") (pin "1") (pinfunction "RT_CLK_1") (pintype "passive"))
      (node (ref "R14") (pin "2") (pinfunction "2_2") (pintype "passive"))
    )
    (net (code "75") (name "Net-(DD3-SS_TR)") (class "Default")
      (node (ref "C18") (pin "1") (pinfunction "1_1") (pintype "passive"))
      (node (ref "DD3") (pin "56") (pinfunction "SS_TR_56") (pintype "passive"))
    )
    (net (code "76") (name "Net-(DD3-VSENSE)") (class "Default")
      (node (ref "DD3") (pin "3") (pinfunction "VSENSE_3") (pintype "passive"))
      (node (ref "R15") (pin "1") (pinfunction "1_1") (pintype "passive"))
      (node (ref "R16") (pin "2") (pinfunction "2_2") (pintype "passive"))
    )
    (net (code "77") (name "Net-(HL1-Pad1)") (class "Default")
      (node (ref "HL1") (pin "1") (pinfunction "1_1") (pintype "passive"))
      (node (ref "R7") (pin "1") (pinfunction "1_1") (pintype "passive"))
    )
    (net (code "78") (name "Net-(HL2-Pad1)") (class "Default")
      (node (ref "HL2") (pin "1") (pinfunction "1_1") (pintype "passive"))
      (node (ref "R17") (pin "1") (pinfunction "1_1") (pintype "passive"))
    )
    (net (code "79") (name "Net-(R3-Pad1)") (class "Default")
      (node (ref "R3") (pin "1") (pinfunction "1_1") (pintype "passive"))
      (node (ref "TP1") (pin "1") (pinfunction "1_1") (pintype "passive"))
    )
    (net (code "80") (name "Net-(R4-Pad1)") (class "Default")
      (node (ref "R4") (pin "1") (pinfunction "1_1") (pintype "passive"))
      (node (ref "TP2") (pin "1") (pinfunction "1_1") (pintype "passive"))
    )
    (net (code "81") (name "Net-(R5-Pad1)") (class "Default")
      (node (ref "R5") (pin "1") (pinfunction "1_1") (pintype "passive"))
      (node (ref "TP3") (pin "1") (pinfunction "1_1") (pintype "passive"))
    )
    (net (code "82") (name "Net-(VT1-133)") (class "Default")
      (node (ref "R18") (pin "2") (pinfunction "2_2") (pintype "passive"))
      (node (ref "VT1") (pin "G") (pinfunction "133_G") (pintype "passive"))
    )
    (net (code "83") (name "Net-(VT2-133)") (class "Default")
      (node (ref "R21") (pin "2") (pinfunction "2_2") (pintype "passive"))
      (node (ref "VT2") (pin "G") (pinfunction "133_G") (pintype "passive"))
    )
    (net (code "84") (name "Net-(VT3-133)") (class "Default")
      (node (ref "R19") (pin "2") (pinfunction "2_2") (pintype "passive"))
      (node (ref "VT3") (pin "G") (pinfunction "133_G") (pintype "passive"))
    )
    (net (code "85") (name "Net-(VT4-133)") (class "Default")
      (node (ref "R22") (pin "2") (pinfunction "2_2") (pintype "passive"))
      (node (ref "VT4") (pin "G") (pinfunction "133_G") (pintype "passive"))
    )
    (net (code "86") (name "Net-(VT5-133)") (class "Default")
      (node (ref "R20") (pin "2") (pinfunction "2_2") (pintype "passive"))
      (node (ref "VT5") (pin "G") (pinfunction "133_G") (pintype "passive"))
    )
    (net (code "87") (name "Net-(VT6-133)") (class "Default")
      (node (ref "R23") (pin "2") (pinfunction "2_2") (pintype "passive"))
      (node (ref "VT6") (pin "G") (pinfunction "133_G") (pintype "passive"))
    )
    (net (code "88") (name "SH1_A") (class "Default")
      (node (ref "C31") (pin "1") (pinfunction "1_1") (pintype "passive"))
      (node (ref "DD3") (pin "46") (pinfunction "SH_A_46") (pintype "passive"))
      (node (ref "R30") (pin "1") (pinfunction "1_1") (pintype "passive"))
      (node (ref "VT1") (pin "S") (pinfunction "134_S") (pintype "passive"))
      (node (ref "VT2") (pin "D") (pinfunction "135_D") (pintype "passive"))
      (node (ref "XP4") (pin "a4") (pinfunction "a4_a4") (pintype "passive"))
      (node (ref "XP4") (pin "c2") (pinfunction "c2_c2") (pintype "passive"))
    )
    (net (code "89") (name "SH1_B") (class "Default")
      (node (ref "C32") (pin "1") (pinfunction "1_1") (pintype "passive"))
      (node (ref "DD3") (pin "41") (pinfunction "SH_B_41") (pintype "passive"))
      (node (ref "R31") (pin "1") (pinfunction "1_1") (pintype "passive"))
      (node (ref "VT3") (pin "S") (pinfunction "134_S") (pintype "passive"))
      (node (ref "VT4") (pin "D") (pinfunction "135_D") (pintype "passive"))
      (node (ref "XP4") (pin "a2") (pinfunction "a2_a2") (pintype "passive"))
    )
    (net (code "90") (name "SH1_C") (class "Default")
      (node (ref "C29") (pin "1") (pinfunction "1_1") (pintype "passive"))
      (node (ref "DD3") (pin "36") (pinfunction "SH_C_36") (pintype "passive"))
      (node (ref "R29") (pin "1") (pinfunction "1_1") (pintype "passive"))
      (node (ref "VT5") (pin "S") (pinfunction "134_S") (pintype "passive"))
      (node (ref "VT6") (pin "D") (pinfunction "135_D") (pintype "passive"))
      (node (ref "XP4") (pin "b4") (pinfunction "b4_b4") (pintype "passive"))
      (node (ref "XP4") (pin "c4") (pinfunction "c4_c4") (pintype "passive"))
    )
    (net (code "91") (name "SL1_A") (class "Default")
      (node (ref "C37") (pin "1") (pinfunction "1_1") (pintype "passive"))
      (node (ref "C40") (pin "2") (pinfunction "2_2") (pintype "passive"))
      (node (ref "DD3") (pin "32") (pinfunction "SP1_32") (pintype "passive"))
      (node (ref "DD3") (pin "44") (pinfunction "SL_A_44") (pintype "passive"))
      (node (ref "R24") (pin "2") (pinfunction "2_2") (pintype "passive"))
      (node (ref "VT2") (pin "S") (pinfunction "134_S") (pintype "passive"))
    )
    (net (code "92") (name "SL1_B") (class "Default")
      (node (ref "C38") (pin "1") (pinfunction "1_1") (pintype "passive"))
      (node (ref "C41") (pin "2") (pinfunction "2_2") (pintype "passive"))
      (node (ref "DD3") (pin "30") (pinfunction "SP2_30") (pintype "passive"))
      (node (ref "DD3") (pin "39") (pinfunction "SL_B_39") (pintype "passive"))
      (node (ref "R25") (pin "2") (pinfunction "2_2") (pintype "passive"))
      (node (ref "VT4") (pin "S") (pinfunction "134_S") (pintype "passive"))
    )
    (net (code "93") (name "SL1_C") (class "Default")
      (node (ref "C42") (pin "2") (pinfunction "2_2") (pintype "passive"))
      (node (ref "C46") (pin "1") (pinfunction "1_1") (pintype "passive"))
      (node (ref "DD3") (pin "34") (pinfunction "SL_C_34") (pintype "passive"))
      (node (ref "R27") (pin "2") (pinfunction "2_2") (pintype "passive"))
      (node (ref "R35") (pin "2") (pinfunction "2_2") (pintype "passive"))
      (node (ref "VT6") (pin "S") (pinfunction "134_S") (pintype "passive"))
    )
    (net (code "94") (name "U1_PH_A") (class "Default")
      (node (ref "C48") (pin "1") (pinfunction "1_1") (pintype "passive"))
      (node (ref "R30") (pin "2") (pinfunction "2_2") (pintype "passive"))
      (node (ref "R33") (pin "1") (pinfunction "1_1") (pintype "passive"))
    )
    (net (code "95") (name "U1_PH_B") (class "Default")
      (node (ref "C49") (pin "1") (pinfunction "1_1") (pintype "passive"))
      (node (ref "R31") (pin "2") (pinfunction "2_2") (pintype "passive"))
      (node (ref "R34") (pin "1") (pinfunction "1_1") (pintype "passive"))
    )
    (net (code "96") (name "U1_PH_C") (class "Default")
      (node (ref "C47") (pin "1") (pinfunction "1_1") (pintype "passive"))
      (node (ref "R29") (pin "2") (pinfunction "2_2") (pintype "passive"))
      (node (ref "R32") (pin "1") (pinfunction "1_1") (pintype "passive"))
    )
    (net (code "97") (name "unconnected-(DD1A-PA1{slash}OP1+{slash}OP3+-Pad13)") (class "Default")
      (node (ref "DD1") (pin "13") (pinfunction "PA1/OP1+/OP3+_13") (pintype "bidirectional"))
    )
    (net (code "98") (name "unconnected-(DD1A-PA3{slash}OP1-{slash}OP1+-Pad17)") (class "Default")
      (node (ref "DD1") (pin "17") (pinfunction "PA3/OP1-/OP1+_17") (pintype "bidirectional"))
    )
    (net (code "99") (name "unconnected-(DD1A-PA5{slash}OP2--Pad19)") (class "Default")
      (node (ref "DD1") (pin "19") (pinfunction "PA5/OP2-_19") (pintype "bidirectional"))
    )
    (net (code "100") (name "unconnected-(DD1A-PA7{slash}OP1+{slash}OP2+-Pad21)") (class "Default")
      (node (ref "DD1") (pin "21") (pinfunction "PA7/OP1+/OP2+_21") (pintype "bidirectional"))
    )
    (net (code "101") (name "unconnected-(DD1A-PA8-Pad42)") (class "Default")
      (node (ref "DD1") (pin "42") (pinfunction "PA8_42") (pintype "bidirectional"))
    )
    (net (code "102") (name "unconnected-(DD1A-PA9-Pad43)") (class "Default")
      (node (ref "DD1") (pin "43") (pinfunction "PA9_43") (pintype "bidirectional"))
    )
    (net (code "103") (name "unconnected-(DD1A-PA10-Pad44)") (class "Default")
      (node (ref "DD1") (pin "44") (pinfunction "PA10_44") (pintype "bidirectional"))
    )
    (net (code "104") (name "unconnected-(DD1A-PA15-Pad51)") (class "Default")
      (node (ref "DD1") (pin "51") (pinfunction "PA15_51") (pintype "bidirectional"))
    )
    (net (code "105") (name "unconnected-(DD1A-PB5-Pad58)") (class "Default")
      (node (ref "DD1") (pin "58") (pinfunction "PB5_58") (pintype "bidirectional"))
    )
    (net (code "106") (name "unconnected-(DD1A-PB6-Pad59)") (class "Default")
      (node (ref "DD1") (pin "59") (pinfunction "PB6_59") (pintype "bidirectional"))
    )
    (net (code "107") (name "unconnected-(DD1A-PB7-Pad60)") (class "Default")
      (node (ref "DD1") (pin "60") (pinfunction "PB7_60") (pintype "bidirectional"))
    )
    (net (code "108") (name "unconnected-(DD1A-PB8-Pad61)") (class "Default")
      (node (ref "DD1") (pin "61") (pinfunction "PB8_61") (pintype "bidirectional"))
    )
    (net (code "109") (name "unconnected-(DD1A-PB8_BOOT0-Pad61)") (class "Default")
      (node (ref "DD1") (pin "61") (pinfunction "PB8_BOOT0_61") (pintype "input"))
    )
    (net (code "110") (name "unconnected-(DD1A-PB9-Pad62)") (class "Default")
      (node (ref "DD1") (pin "62") (pinfunction "PB9_62") (pintype "bidirectional"))
    )
    (net (code "111") (name "unconnected-(DD1A-PB10{slash}OP3--Pad30)") (class "Default")
      (node (ref "DD1") (pin "30") (pinfunction "PB10/OP3-_30") (pintype "bidirectional"))
    )
    (net (code "112") (name "unconnected-(DD1A-PB12-Pad34)") (class "Default")
      (node (ref "DD1") (pin "34") (pinfunction "PB12_34") (pintype "bidirectional"))
    )
    (net (code "113") (name "unconnected-(DD1A-PB13{slash}OP3+-Pad35)") (class "Default")
      (node (ref "DD1") (pin "35") (pinfunction "PB13/OP3+_35") (pintype "bidirectional"))
    )
    (net (code "114") (name "unconnected-(DD1A-PB14{slash}OP2+-Pad36)") (class "Default")
      (node (ref "DD1") (pin "36") (pinfunction "PB14/OP2+_36") (pintype "bidirectional"))
    )
    (net (code "115") (name "unconnected-(DD1A-PC3-Pad11)") (class "Default")
      (node (ref "DD1") (pin "11") (pinfunction "PC3_11") (pintype "bidirectional"))
    )
    (net (code "116") (name "unconnected-(DD1A-PC4-Pad22)") (class "Default")
      (node (ref "DD1") (pin "22") (pinfunction "PC4_22") (pintype "bidirectional"))
    )
    (net (code "117") (name "unconnected-(DD1A-PC5{slash}OP1-{slash}OP2--Pad23)") (class "Default")
      (node (ref "DD1") (pin "23") (pinfunction "PC5/OP1-/OP2-_23") (pintype "bidirectional"))
    )
    (net (code "118") (name "unconnected-(DD1A-PC9-Pad41)") (class "Default")
      (node (ref "DD1") (pin "41") (pinfunction "PC9_41") (pintype "bidirectional"))
    )
    (net (code "119") (name "unconnected-(DD2-SHDN-Pad5)") (class "Default")
      (node (ref "DD2") (pin "5") (pinfunction "SHDN_5") (pintype "passive"))
    )
    (net (code "120") (name "unconnected-(DD3-DC_CAL-Pad12)") (class "Default")
      (node (ref "DD3") (pin "12") (pinfunction "DC_CAL_12") (pintype "passive"))
    )
    (net (code "121") (name "unconnected-(DD3-EN_BUCK-Pad55)") (class "Default")
      (node (ref "DD3") (pin "55") (pinfunction "EN_BUCK_55") (pintype "passive"))
    )
    (net (code "122") (name "unconnected-(XP4-Padb2)") (class "Default")
      (node (ref "XP4") (pin "b2") (pinfunction "b2_b2") (pintype "passive"))
    )
  )
)
